# Mouse_Project.net
KiCad netlist of a schematic drawn in Altium Designer
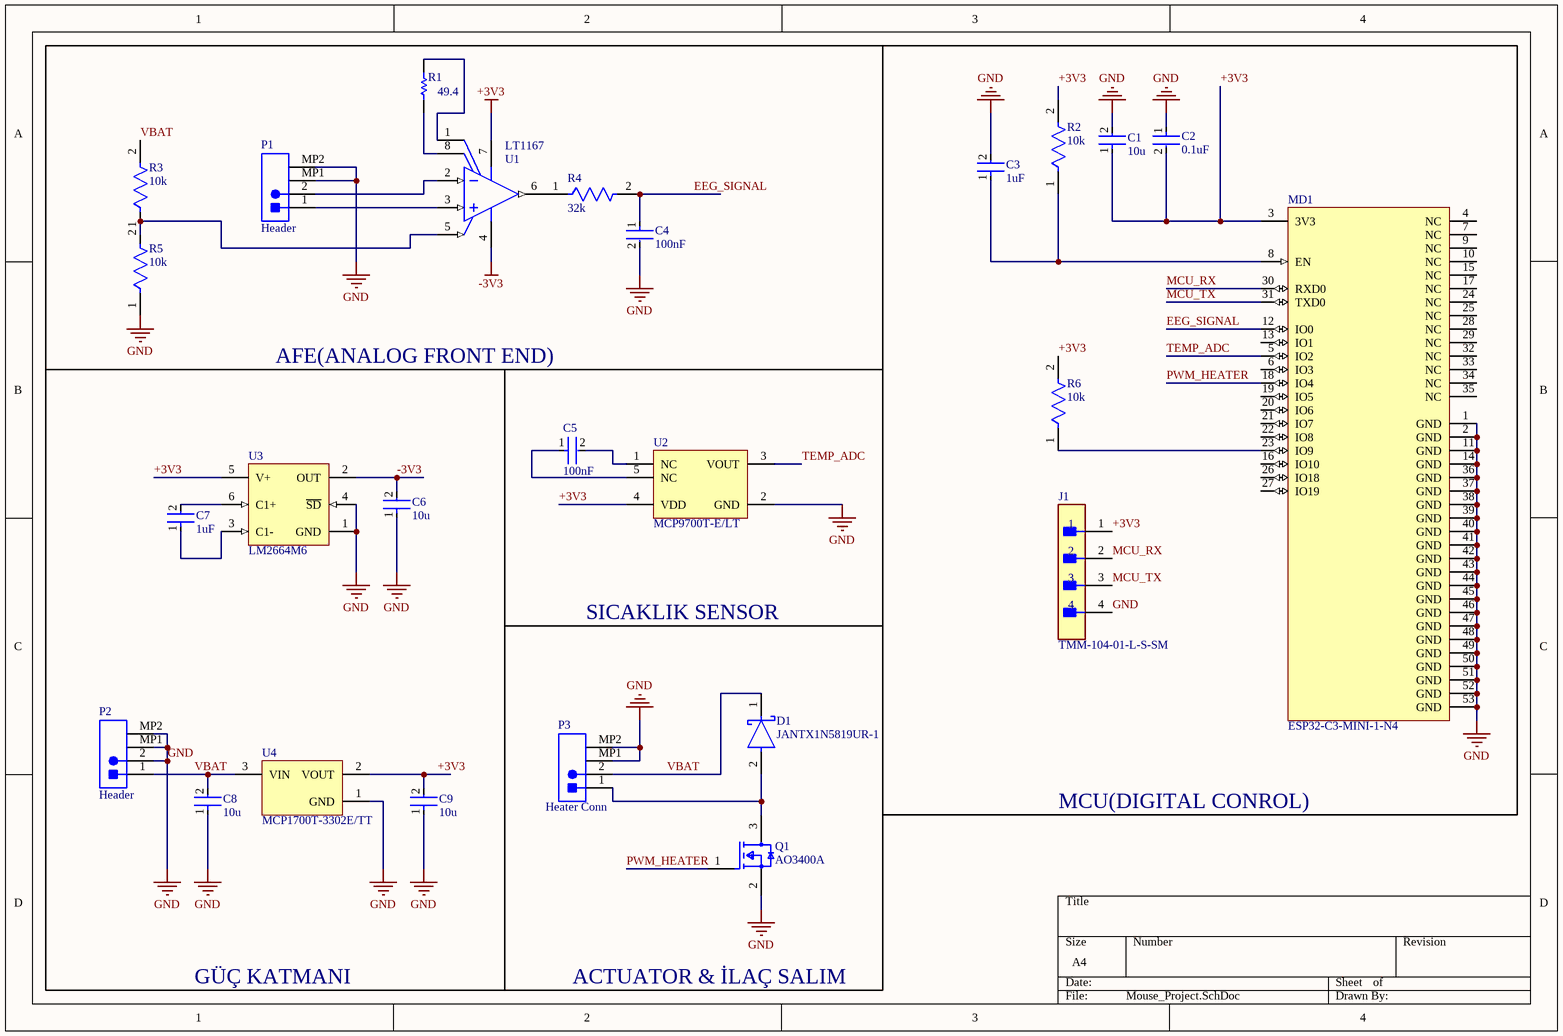
[diagram p0: Mouse_Project.SchDoc]

(export (version "E")
  (design (tool "Eeschema 10.0.6"))
  (components
    (comp (ref "C1")
      (value "10u")
      (footprint "FP-CC0603-DC-IPC_A")
      (description "CAP CER 10UF 10V X5R 0603")
      (fields (field (name "TOLERANCE") "10%"))
      (libsource (lib "Altium Content Vault") (part "b4654b650e69147ec39a6b967a45e02"))
    )
    (comp (ref "C2")
      (value "0.1uF")
      (footprint "FP-C0603C-CF-MFG")
      (description "CAP CER 0.1UF 50V X7R 0603")
      (fields (field (name "TOLERANCE") "0.1") (field (name "MANUFACTURER") "KEMET"))
      (libsource (lib "Altium Content Vault") (part "b4654b650e69147ec39a6b967a45e02"))
    )
    (comp (ref "C3")
      (value "1uF")
      (footprint "FP-CL10-IPC_C")
      (description "Cap Ceramic 1uF 25V X5R ±10% Pad SMD 0603 +85°C T/R")
      (fields (field (name "VOLTAGE") "25V") (field (name "TOLERANCE") "10%"))
      (libsource (lib "Altium Content Vault") (part "b4654b650e69147ec39a6b967a45e02"))
    )
    (comp (ref "C4")
      (value "100nF")
      (footprint "FP-CL21-IPC_B")
      (description "CL21 Series 0805 100nF 25V -20/+80% Tolerance Y5V Multilayer Ceramic Chip Capacitor")
      (libsource (lib "Altium Content Vault") (part "b4654b650e69147ec39a6b967a45e02"))
    )
    (comp (ref "C5")
      (value "100nF")
      (footprint "FP-CL21-IPC_B")
      (description "CL21 Series 0805 100nF 25V -20/+80% Tolerance Y5V Multilayer Ceramic Chip Capacitor")
      (libsource (lib "Altium Content Vault") (part "b4654b650e69147ec39a6b967a45e02"))
    )
    (comp (ref "C6")
      (value "10u")
      (footprint "FP-CC0603-DC-IPC_A")
      (description "CAP CER 10UF 10V X5R 0603")
      (fields (field (name "TOLERANCE") "10%"))
      (libsource (lib "Altium Content Vault") (part "b4654b650e69147ec39a6b967a45e02"))
    )
    (comp (ref "C7")
      (value "1uF")
      (footprint "FP-CL10-IPC_C")
      (description "Cap Ceramic 1uF 25V X5R ±10% Pad SMD 0603 +85°C T/R")
      (fields (field (name "VOLTAGE") "25V") (field (name "TOLERANCE") "10%"))
      (libsource (lib "Altium Content Vault") (part "b4654b650e69147ec39a6b967a45e02"))
    )
    (comp (ref "C8")
      (value "10u")
      (footprint "FP-CC0603-DC-IPC_A")
      (description "CAP CER 10UF 10V X5R 0603")
      (fields (field (name "TOLERANCE") "10%"))
      (libsource (lib "Altium Content Vault") (part "b4654b650e69147ec39a6b967a45e02"))
    )
    (comp (ref "C9")
      (value "10u")
      (footprint "FP-CC0603-DC-IPC_A")
      (description "CAP CER 10UF 10V X5R 0603")
      (fields (field (name "TOLERANCE") "10%"))
      (libsource (lib "Altium Content Vault") (part "b4654b650e69147ec39a6b967a45e02"))
    )
    (comp (ref "D1")
      (value "JANTX1N5819UR-1")
      (footprint "FP-DO-213AB-MFG")
      (description "DIODE SCHOTTKY 45V 1A DO213AB")
      (libsource (lib "Altium Content Vault") (part "1d6ec82d83fb6aee721767c19dac4b9"))
    )
    (comp (ref "J1")
      (value "TMM-104-01-L-S-SM")
      (footprint "FP-TMM-104-01-L-S-SM-MFG")
      (description "CONN HEADER SMD 4POS 2MM")
      (libsource (lib "Altium Content Vault") (part "299a8cea1bdcbc3624fe62c390fa72c"))
    )
    (comp (ref "MD1")
      (value "ESP32-C3-MINI-1-N4")
      (footprint "FP-ESP32-C3-MINI-1-N4-MFG")
      (description "Multiprotocol Modules SMD module, ESP32-C3FN4, PCB antenna, -40 C +85 C")
      (libsource (lib "Altium Content Vault") (part "ESP32-C3-MINI-1-N4"))
    )
    (comp (ref "P1")
      (value "Header")
      (footprint "MOLX-53261-0271_V")
      (description "PicoBlade(TM) Header, Right Angle, -40 to 85 degC, 2-Pin SMD, RoHS, Tape and Reel")
      (fields (field (name "MANUFACTURER") "Molex"))
      (libsource (lib "Altium Content Vault") (part "CN-1P-2M-R2"))
    )
    (comp (ref "P2")
      (value "Header")
      (footprint "MOLX-53261-0271_V")
      (description "PicoBlade(TM) Header, Right Angle, -40 to 85 degC, 2-Pin SMD, RoHS, Tape and Reel")
      (fields (field (name "MANUFACTURER") "Molex"))
      (libsource (lib "Altium Content Vault") (part "CN-1P-2M-R2"))
    )
    (comp (ref "P3")
      (value "Heater Conn")
      (footprint "MOLX-53261-0271_V")
      (description "PicoBlade(TM) Header, Right Angle, -40 to 85 degC, 2-Pin SMD, RoHS, Tape and Reel")
      (fields (field (name "MANUFACTURER") "Molex"))
      (libsource (lib "Altium Content Vault") (part "CN-1P-2M-R2"))
    )
    (comp (ref "Q1")
      (value "AO3400A")
      (footprint "FP-SOT23-MFG")
      (description "MOSFET N-CH 30V 5.7A SOT23")
      (libsource (lib "Altium Content Vault") (part "0a9ea7c96deaaede766a5b531c28de0"))
    )
    (comp (ref "R1")
      (value "49.4")
      (footprint "RESC1608X55X30ML15T15")
      (fields (field (name "MANUFACTURER") "Panasonic") (field (name "PART NUMBER") "ERJ-3EKF49R9V"))
      (libsource (lib "Altium Content Vault") (part "RES"))
    )
    (comp (ref "R2")
      (value "10k")
      (footprint "FP-RT0805-MFG")
      (description "RES SMD 10.2K OHM 0.5% 1/8W 0805")
      (fields
        (field (name "OCTOPART") "https://octopart.com/rt0805drd0710k2l-yageo-1441674")
        (field (name "MANUFACTURER") "Yageo")
      )
      (libsource (lib "Altium Content Vault") (part "1029c3af85768c4190bb7ad29bc67b5"))
    )
    (comp (ref "R3")
      (value "10k")
      (footprint "FP-RT0805-MFG")
      (description "RES SMD 10.2K OHM 0.5% 1/8W 0805")
      (fields
        (field (name "OCTOPART") "https://octopart.com/rt0805drd0710k2l-yageo-1441674")
        (field (name "MANUFACTURER") "Yageo")
      )
      (libsource (lib "Altium Content Vault") (part "1029c3af85768c4190bb7ad29bc67b5"))
    )
    (comp (ref "R4")
      (value "32k")
      (footprint "FP-RT0805-MFG")
      (description "RES SMD 332K OHM 0.1% 1/8W 0805")
      (fields
        (field (name "MANUFACTURER") "Yageo")
        (field (name "OCTOPART") "https://octopart.com/rt0805bre07332kl-yageo-1228961")
      )
      (libsource (lib "Altium Content Vault") (part "1029c3af85768c4190bb7ad29bc67b5"))
    )
    (comp (ref "R5")
      (value "10k")
      (footprint "FP-RT0805-MFG")
      (description "RES SMD 10.2K OHM 0.5% 1/8W 0805")
      (fields
        (field (name "OCTOPART") "https://octopart.com/rt0805drd0710k2l-yageo-1441674")
        (field (name "MANUFACTURER") "Yageo")
      )
      (libsource (lib "Altium Content Vault") (part "1029c3af85768c4190bb7ad29bc67b5"))
    )
    (comp (ref "R6")
      (value "10k")
      (footprint "FP-RT0805-MFG")
      (description "RES SMD 10.2K OHM 0.5% 1/8W 0805")
      (fields
        (field (name "OCTOPART") "https://octopart.com/rt0805drd0710k2l-yageo-1441674")
        (field (name "MANUFACTURER") "Yageo")
      )
      (libsource (lib "Altium Content Vault") (part "1029c3af85768c4190bb7ad29bc67b5"))
    )
    (comp (ref "U1")
      (value "LT1167")
      (footprint "LT-S8-8_M")
      (fields (field (name "PARTNUMBER") "LT1167AIS8#PBF") (field (name "MANUFACTURER") "Linear Technology"))
      (libsource (lib "Altium Content Vault") (part "LT-LT1167-S8-8"))
    )
    (comp (ref "U2")
      (value "MCP9700T-E/LT")
      (footprint "SC70-LT5_M")
      (description "Low-Power Linear Active Thermistor IC, 5-Pin SC-70, Extended Temperature, Tape and Reel")
      (libsource (lib "Altium Content Vault") (part "SEN-TEMP-MCP9700-5"))
    )
    (comp (ref "U3")
      (value "LM2664M6")
      (footprint "DBV0006A_N")
      (description "Switched Capacitor Voltage Converter, 6-pin SOT-23")
      (fields (field (name "MANUFACTURER") "Texas Instruments"))
      (libsource (lib "Altium Content Vault") (part "PM-CHP-LM2664M6-6"))
    )
    (comp (ref "U4")
      (value "MCP1700T-3302E/TT")
      (footprint "SOT-23-TT3_N")
      (description "Low Quiescent Current LDO, 3-Pin SOT-23, Extended Temperature, Tape and Reel")
      (libsource (lib "Altium Content Vault") (part "PM-LINEREG-MCP1700-IL3"))
    )
  )
  (nets
    (net (code "1") (name "+3V3") (class "Default")
      (node (ref "C1") (pin "1") (pinfunction "1_1") (pintype "passive"))
      (node (ref "C2") (pin "2") (pinfunction "2_2") (pintype "passive"))
      (node (ref "C9") (pin "2") (pinfunction "2_2") (pintype "passive"))
      (node (ref "J1") (pin "1") (pinfunction "1_1") (pintype "passive"))
      (node (ref "MD1") (pin "3") (pinfunction "3V3_3") (pintype "power_in"))
      (node (ref "R2") (pin "2") (pinfunction "2_2") (pintype "passive"))
      (node (ref "R6") (pin "2") (pinfunction "2_2") (pintype "passive"))
      (node (ref "U1") (pin "7") (pinfunction "+VS_7") (pintype "power_in"))
      (node (ref "U2") (pin "4") (pinfunction "VDD_4") (pintype "power_in"))
      (node (ref "U3") (pin "5") (pinfunction "V+_5") (pintype "power_in"))
      (node (ref "U4") (pin "2") (pinfunction "VOUT_2") (pintype "power_in"))
    )
    (net (code "2") (name "-3V3") (class "Default")
      (node (ref "C6") (pin "2") (pinfunction "2_2") (pintype "passive"))
      (node (ref "U1") (pin "4") (pinfunction "-VS_4") (pintype "power_in"))
      (node (ref "U3") (pin "2") (pinfunction "OUT_2") (pintype "power_in"))
    )
    (net (code "3") (name "/EEG_SIGNAL") (class "Default")
      (node (ref "C4") (pin "1") (pinfunction "1_1") (pintype "passive"))
      (node (ref "MD1") (pin "12") (pinfunction "IO0_12") (pintype "bidirectional"))
      (node (ref "R4") (pin "2") (pinfunction "2_2") (pintype "passive"))
    )
    (net (code "4") (name "/MCU_RX") (class "Default")
      (node (ref "J1") (pin "2") (pinfunction "2_2") (pintype "passive"))
      (node (ref "MD1") (pin "30") (pinfunction "RXD0_30") (pintype "bidirectional"))
    )
    (net (code "5") (name "/MCU_TX") (class "Default")
      (node (ref "J1") (pin "3") (pinfunction "3_3") (pintype "passive"))
      (node (ref "MD1") (pin "31") (pinfunction "TXD0_31") (pintype "bidirectional"))
    )
    (net (code "6") (name "/PWM_HEATER") (class "Default")
      (node (ref "MD1") (pin "18") (pinfunction "IO4_18") (pintype "bidirectional"))
      (node (ref "Q1") (pin "1") (pinfunction "G_1") (pintype "passive"))
    )
    (net (code "7") (name "/TEMP_ADC") (class "Default")
      (node (ref "MD1") (pin "5") (pinfunction "IO2_5") (pintype "bidirectional"))
      (node (ref "U2") (pin "3") (pinfunction "VOUT_3") (pintype "power_in"))
    )
    (net (code "8") (name "/VBAT") (class "Default")
      (node (ref "C8") (pin "2") (pinfunction "2_2") (pintype "passive"))
      (node (ref "D1") (pin "1") (pinfunction "C_1") (pintype "passive"))
      (node (ref "P2") (pin "1") (pinfunction "1_1") (pintype "passive"))
      (node (ref "P3") (pin "2") (pinfunction "2_2") (pintype "passive"))
      (node (ref "R3") (pin "2") (pinfunction "2_2") (pintype "passive"))
      (node (ref "U4") (pin "3") (pinfunction "VIN_3") (pintype "power_in"))
    )
    (net (code "9") (name "GND") (class "Default")
      (node (ref "C1") (pin "2") (pinfunction "2_2") (pintype "passive"))
      (node (ref "C2") (pin "1") (pinfunction "1_1") (pintype "passive"))
      (node (ref "C3") (pin "2") (pinfunction "2_2") (pintype "passive"))
      (node (ref "C4") (pin "2") (pinfunction "2_2") (pintype "passive"))
      (node (ref "C6") (pin "1") (pinfunction "1_1") (pintype "passive"))
      (node (ref "C8") (pin "1") (pinfunction "1_1") (pintype "passive"))
      (node (ref "C9") (pin "1") (pinfunction "1_1") (pintype "passive"))
      (node (ref "J1") (pin "4") (pinfunction "4_4") (pintype "passive"))
      (node (ref "MD1") (pin "1") (pinfunction "GND_1") (pintype "power_in"))
      (node (ref "MD1") (pin "11") (pinfunction "GND_11") (pintype "power_in"))
      (node (ref "MD1") (pin "14") (pinfunction "GND_14") (pintype "power_in"))
      (node (ref "MD1") (pin "2") (pinfunction "GND_2") (pintype "power_in"))
      (node (ref "MD1") (pin "36") (pinfunction "GND_36") (pintype "power_in"))
      (node (ref "MD1") (pin "37") (pinfunction "GND_37") (pintype "power_in"))
      (node (ref "MD1") (pin "38") (pinfunction "GND_38") (pintype "power_in"))
      (node (ref "MD1") (pin "39") (pinfunction "GND_39") (pintype "power_in"))
      (node (ref "MD1") (pin "40") (pinfunction "GND_40") (pintype "power_in"))
      (node (ref "MD1") (pin "41") (pinfunction "GND_41") (pintype "power_in"))
      (node (ref "MD1") (pin "42") (pinfunction "GND_42") (pintype "power_in"))
      (node (ref "MD1") (pin "43") (pinfunction "GND_43") (pintype "power_in"))
      (node (ref "MD1") (pin "44") (pinfunction "GND_44") (pintype "power_in"))
      (node (ref "MD1") (pin "45") (pinfunction "GND_45") (pintype "power_in"))
      (node (ref "MD1") (pin "46") (pinfunction "GND_46") (pintype "power_in"))
      (node (ref "MD1") (pin "47") (pinfunction "GND_47") (pintype "power_in"))
      (node (ref "MD1") (pin "48") (pinfunction "GND_48") (pintype "power_in"))
      (node (ref "MD1") (pin "49") (pinfunction "GND_49") (pintype "power_in"))
      (node (ref "MD1") (pin "50") (pinfunction "GND_50") (pintype "power_in"))
      (node (ref "MD1") (pin "51") (pinfunction "GND_51") (pintype "power_in"))
      (node (ref "MD1") (pin "52") (pinfunction "GND_52") (pintype "power_in"))
      (node (ref "MD1") (pin "53") (pinfunction "GND_53") (pintype "power_in"))
      (node (ref "P1") (pin "MP1") (pinfunction "MP1_MP1") (pintype "passive"))
      (node (ref "P1") (pin "MP2") (pinfunction "MP2_MP2") (pintype "passive"))
      (node (ref "P2") (pin "2") (pinfunction "2_2") (pintype "passive"))
      (node (ref "P2") (pin "MP1") (pinfunction "MP1_MP1") (pintype "passive"))
      (node (ref "P2") (pin "MP2") (pinfunction "MP2_MP2") (pintype "passive"))
      (node (ref "P3") (pin "MP1") (pinfunction "MP1_MP1") (pintype "passive"))
      (node (ref "P3") (pin "MP2") (pinfunction "MP2_MP2") (pintype "passive"))
      (node (ref "Q1") (pin "2") (pinfunction "S_2") (pintype "passive"))
      (node (ref "R5") (pin "1") (pinfunction "1_1") (pintype "passive"))
      (node (ref "U2") (pin "2") (pinfunction "GND_2") (pintype "power_in"))
      (node (ref "U3") (pin "1") (pinfunction "GND_1") (pintype "power_in"))
      (node (ref "U3") (pin "4") (pinfunction "~{SD}_4") (pintype "input"))
      (node (ref "U4") (pin "1") (pinfunction "GND_1") (pintype "power_in"))
    )
    (net (code "10") (name "Net-(C5-Pad1)") (class "Default")
      (node (ref "C5") (pin "1") (pinfunction "1_1") (pintype "passive"))
      (node (ref "U2") (pin "5") (pinfunction "NC_5") (pintype "passive"))
    )
    (net (code "11") (name "Net-(C5-Pad2)") (class "Default")
      (node (ref "C5") (pin "2") (pinfunction "2_2") (pintype "passive"))
      (node (ref "U2") (pin "1") (pinfunction "NC_1") (pintype "passive"))
    )
    (net (code "12") (name "Net-(D1-A)") (class "Default")
      (node (ref "D1") (pin "2") (pinfunction "A_2") (pintype "passive"))
      (node (ref "P3") (pin "1") (pinfunction "1_1") (pintype "passive"))
      (node (ref "Q1") (pin "3") (pinfunction "D_3") (pintype "passive"))
    )
    (net (code "13") (name "Net-(MD1-EN)") (class "Default")
      (node (ref "C3") (pin "1") (pinfunction "1_1") (pintype "passive"))
      (node (ref "MD1") (pin "8") (pinfunction "EN_8") (pintype "input"))
      (node (ref "R2") (pin "1") (pinfunction "1_1") (pintype "passive"))
    )
    (net (code "14") (name "Net-(MD1-IO9)") (class "Default")
      (node (ref "MD1") (pin "23") (pinfunction "IO9_23") (pintype "bidirectional"))
      (node (ref "R6") (pin "1") (pinfunction "1_1") (pintype "passive"))
    )
    (net (code "15") (name "Net-(R1-Pad1)") (class "Default")
      (node (ref "R1") (pin "1") (pinfunction "1_1") (pintype "passive"))
      (node (ref "U1") (pin "8") (pinfunction "RG_8") (pintype "passive"))
    )
    (net (code "16") (name "Net-(R1-Pad2)") (class "Default")
      (node (ref "R1") (pin "2") (pinfunction "2_2") (pintype "passive"))
      (node (ref "U1") (pin "1") (pinfunction "RG_1") (pintype "passive"))
    )
    (net (code "17") (name "Net-(U1-+IN)") (class "Default")
      (node (ref "P1") (pin "1") (pinfunction "1_1") (pintype "passive"))
      (node (ref "U1") (pin "3") (pinfunction "+IN_3") (pintype "input"))
    )
    (net (code "18") (name "Net-(U1--IN)") (class "Default")
      (node (ref "P1") (pin "2") (pinfunction "2_2") (pintype "passive"))
      (node (ref "U1") (pin "2") (pinfunction "-IN_2") (pintype "input"))
    )
    (net (code "19") (name "Net-(U1-OUTPUT)") (class "Default")
      (node (ref "R4") (pin "1") (pinfunction "1_1") (pintype "passive"))
      (node (ref "U1") (pin "6") (pinfunction "OUTPUT_6") (pintype "output"))
    )
    (net (code "20") (name "Net-(U1-REF)") (class "Default")
      (node (ref "R3") (pin "1") (pinfunction "1_1") (pintype "passive"))
      (node (ref "R5") (pin "2") (pinfunction "2_2") (pintype "passive"))
      (node (ref "U1") (pin "5") (pinfunction "REF_5") (pintype "input"))
    )
    (net (code "21") (name "Net-(U3-C1+)") (class "Default")
      (node (ref "C7") (pin "2") (pinfunction "2_2") (pintype "passive"))
      (node (ref "U3") (pin "6") (pinfunction "C1+_6") (pintype "input"))
    )
    (net (code "22") (name "Net-(U3-C1-)") (class "Default")
      (node (ref "C7") (pin "1") (pinfunction "1_1") (pintype "passive"))
      (node (ref "U3") (pin "3") (pinfunction "C1-_3") (pintype "input"))
    )
    (net (code "23") (name "unconnected-(MD1-IO1-Pad13)") (class "Default")
      (node (ref "MD1") (pin "13") (pinfunction "IO1_13") (pintype "bidirectional"))
    )
    (net (code "24") (name "unconnected-(MD1-IO3-Pad6)") (class "Default")
      (node (ref "MD1") (pin "6") (pinfunction "IO3_6") (pintype "bidirectional"))
    )
    (net (code "25") (name "unconnected-(MD1-IO5-Pad19)") (class "Default")
      (node (ref "MD1") (pin "19") (pinfunction "IO5_19") (pintype "bidirectional"))
    )
    (net (code "26") (name "unconnected-(MD1-IO6-Pad20)") (class "Default")
      (node (ref "MD1") (pin "20") (pinfunction "IO6_20") (pintype "bidirectional"))
    )
    (net (code "27") (name "unconnected-(MD1-IO7-Pad21)") (class "Default")
      (node (ref "MD1") (pin "21") (pinfunction "IO7_21") (pintype "bidirectional"))
    )
    (net (code "28") (name "unconnected-(MD1-IO8-Pad22)") (class "Default")
      (node (ref "MD1") (pin "22") (pinfunction "IO8_22") (pintype "bidirectional"))
    )
    (net (code "29") (name "unconnected-(MD1-IO10-Pad16)") (class "Default")
      (node (ref "MD1") (pin "16") (pinfunction "IO10_16") (pintype "bidirectional"))
    )
    (net (code "30") (name "unconnected-(MD1-IO18-Pad26)") (class "Default")
      (node (ref "MD1") (pin "26") (pinfunction "IO18_26") (pintype "bidirectional"))
    )
    (net (code "31") (name "unconnected-(MD1-IO19-Pad27)") (class "Default")
      (node (ref "MD1") (pin "27") (pinfunction "IO19_27") (pintype "bidirectional"))
    )
    (net (code "32") (name "unconnected-(MD1-NC-Pad4)") (class "Default")
      (node (ref "MD1") (pin "4") (pinfunction "NC_4") (pintype "passive"))
    )
    (net (code "33") (name "unconnected-(MD1-NC-Pad7)") (class "Default")
      (node (ref "MD1") (pin "7") (pinfunction "NC_7") (pintype "passive"))
    )
    (net (code "34") (name "unconnected-(MD1-NC-Pad9)") (class "Default")
      (node (ref "MD1") (pin "9") (pinfunction "NC_9") (pintype "passive"))
    )
    (net (code "35") (name "unconnected-(MD1-NC-Pad10)") (class "Default")
      (node (ref "MD1") (pin "10") (pinfunction "NC_10") (pintype "passive"))
    )
    (net (code "36") (name "unconnected-(MD1-NC-Pad15)") (class "Default")
      (node (ref "MD1") (pin "15") (pinfunction "NC_15") (pintype "passive"))
    )
    (net (code "37") (name "unconnected-(MD1-NC-Pad17)") (class "Default")
      (node (ref "MD1") (pin "17") (pinfunction "NC_17") (pintype "passive"))
    )
    (net (code "38") (name "unconnected-(MD1-NC-Pad24)") (class "Default")
      (node (ref "MD1") (pin "24") (pinfunction "NC_24") (pintype "passive"))
    )
    (net (code "39") (name "unconnected-(MD1-NC-Pad25)") (class "Default")
      (node (ref "MD1") (pin "25") (pinfunction "NC_25") (pintype "passive"))
    )
    (net (code "40") (name "unconnected-(MD1-NC-Pad28)") (class "Default")
      (node (ref "MD1") (pin "28") (pinfunction "NC_28") (pintype "passive"))
    )
    (net (code "41") (name "unconnected-(MD1-NC-Pad29)") (class "Default")
      (node (ref "MD1") (pin "29") (pinfunction "NC_29") (pintype "passive"))
    )
    (net (code "42") (name "unconnected-(MD1-NC-Pad32)") (class "Default")
      (node (ref "MD1") (pin "32") (pinfunction "NC_32") (pintype "passive"))
    )
    (net (code "43") (name "unconnected-(MD1-NC-Pad33)") (class "Default")
      (node (ref "MD1") (pin "33") (pinfunction "NC_33") (pintype "passive"))
    )
    (net (code "44") (name "unconnected-(MD1-NC-Pad34)") (class "Default")
      (node (ref "MD1") (pin "34") (pinfunction "NC_34") (pintype "passive"))
    )
    (net (code "45") (name "unconnected-(MD1-NC-Pad35)") (class "Default")
      (node (ref "MD1") (pin "35") (pinfunction "NC_35") (pintype "passive"))
    )
  )
)
